# Sheet.net
KiCad netlist of a schematic drawn in Altium Designer
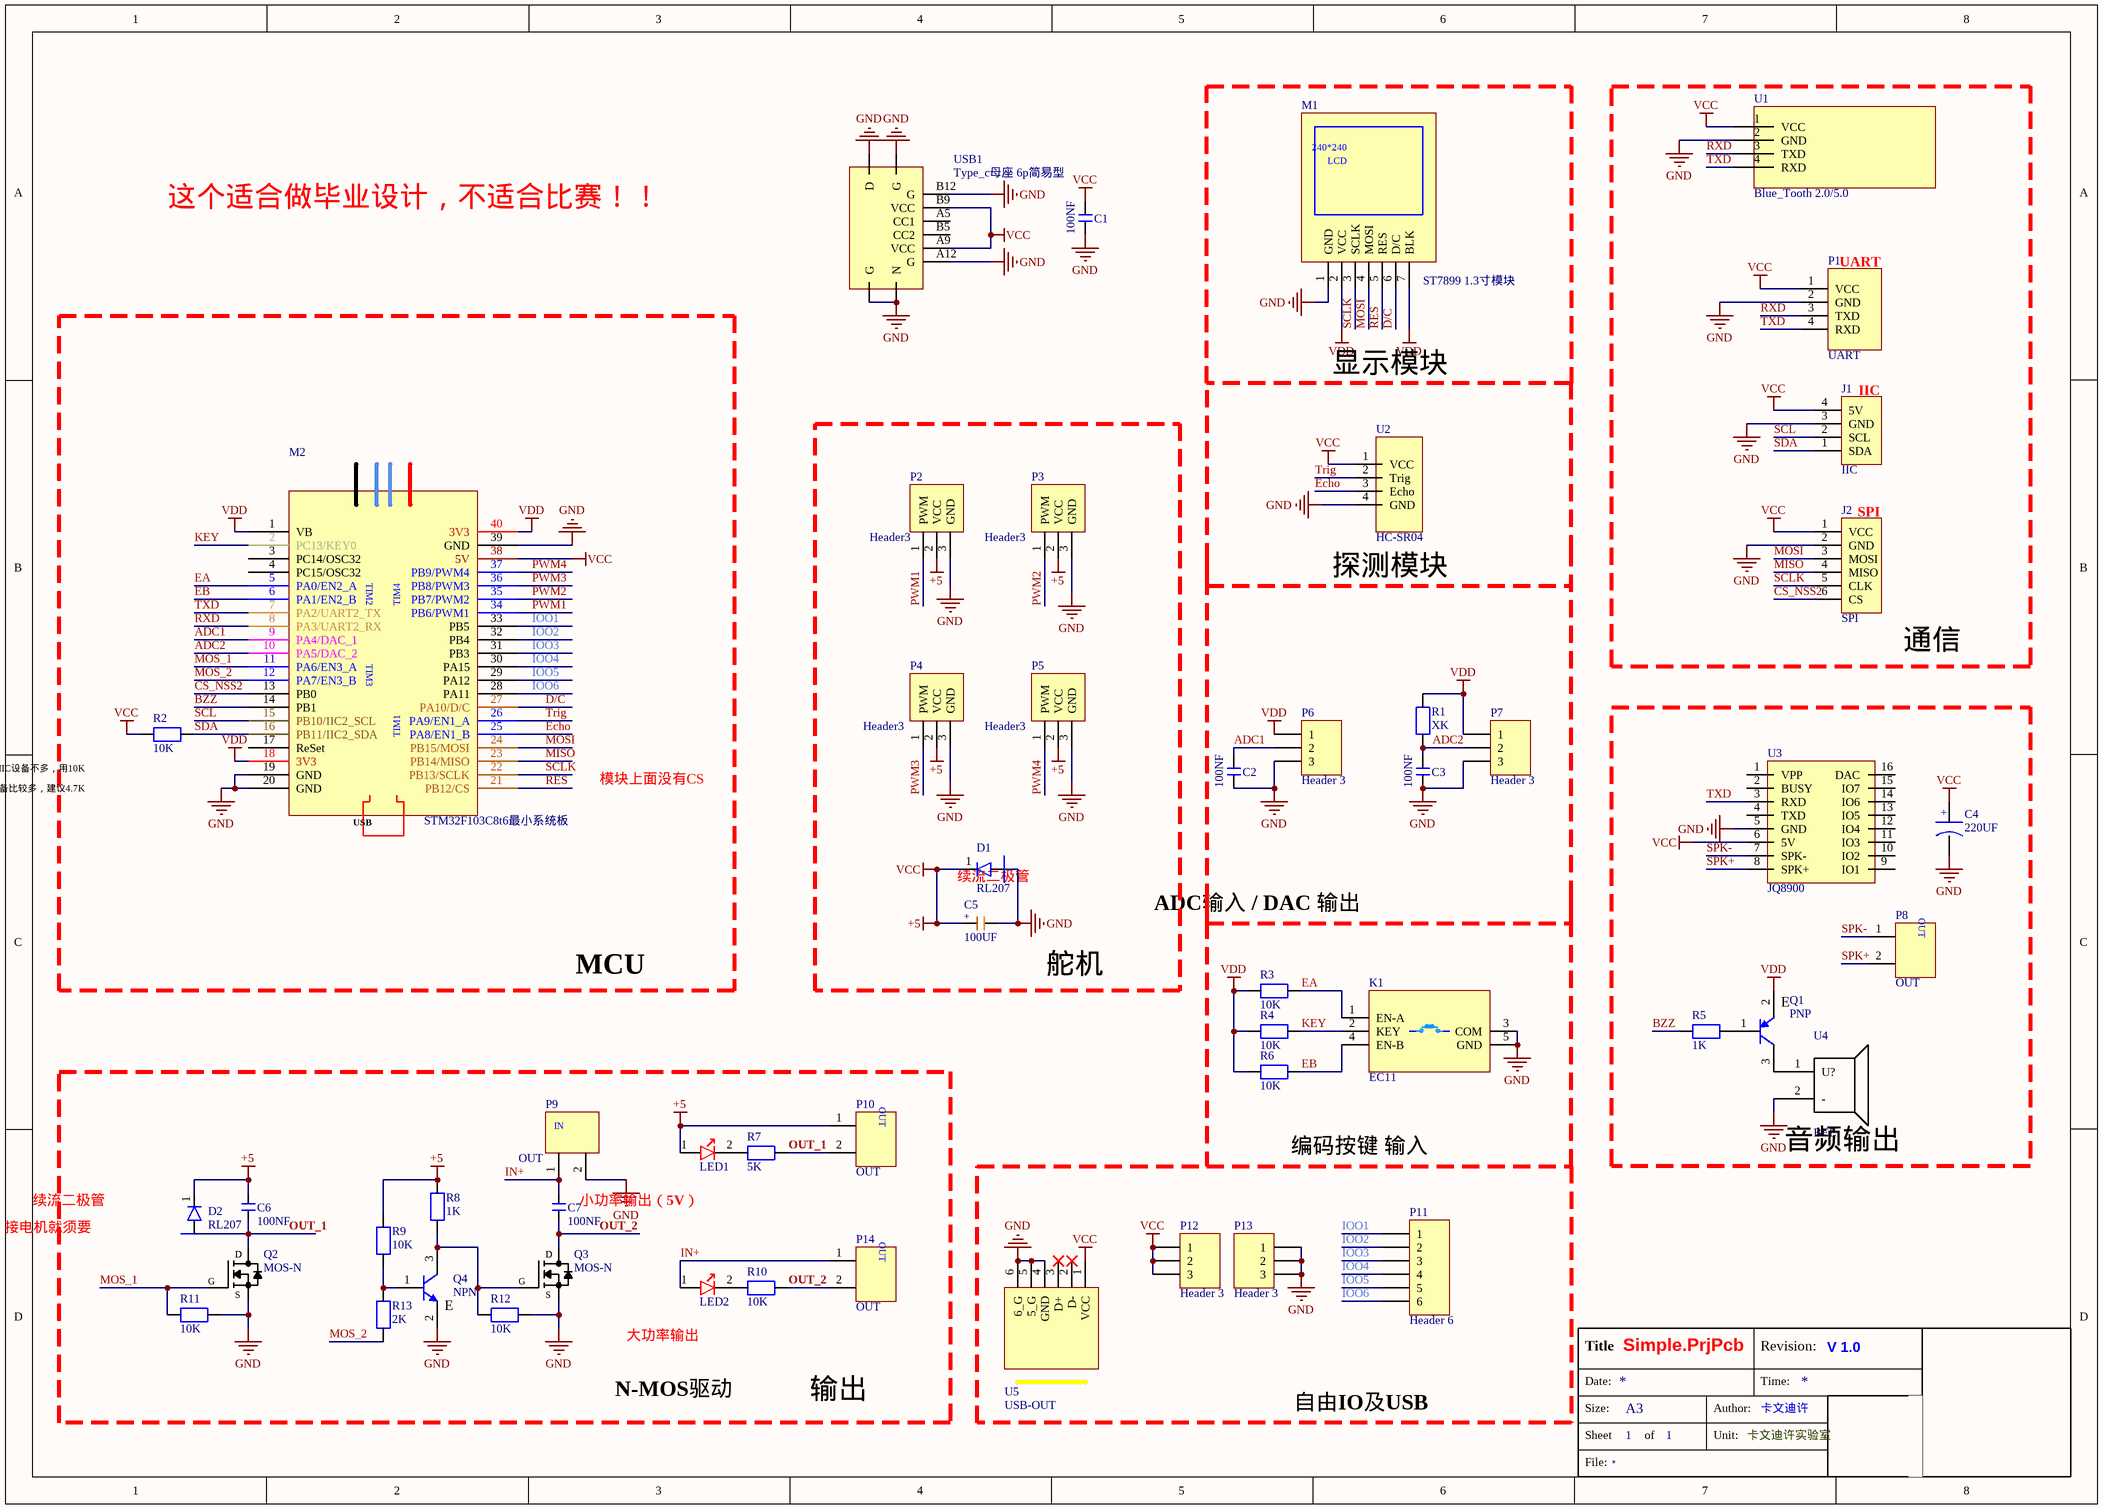
[diagram p0: Sheet.SchDoc]

(export (version "E")
  (design (tool "Eeschema 10.0.6"))
  (components
    (comp (ref "C1")
      (value "100NF")
      (footprint "CAP_0603")
      (description "CAP  12~50V")
      (libsource (lib "") (part "CAP_1"))
    )
    (comp (ref "C2")
      (value "100NF")
      (footprint "CAP_0603")
      (description "CAP  12~50V")
      (libsource (lib "") (part "CAP_1"))
    )
    (comp (ref "C3")
      (value "100NF")
      (footprint "CAP_0603")
      (description "CAP  12~50V")
      (libsource (lib "") (part "CAP_1"))
    )
    (comp (ref "C4")
      (value "220UF")
      (footprint "CAP_PR_2.5_6.3_RA")
      (description "CAP 12V ~ 50V   电解电容")
      (libsource (lib "User") (part "CAP_BIG"))
    )
    (comp (ref "C5")
      (value "100UF")
      (footprint "CAP_3528_B")
      (description "CAP  6~12V  钽电容")
      (libsource (lib "User") (part "CAP_TA"))
    )
    (comp (ref "C6")
      (value "100NF")
      (footprint "CAP_0603")
      (description "CAP  12~50V")
      (libsource (lib "User") (part "CAP"))
    )
    (comp (ref "C7")
      (value "100NF")
      (footprint "CAP_0603")
      (description "CAP  12~50V")
      (libsource (lib "User") (part "CAP"))
    )
    (comp (ref "D1")
      (value "RL207")
      (footprint "Diode_DO15")
      (description "Diode_肖特基/二极管 \r\n直插")
      (libsource (lib "User") (part "Diode-DO"))
    )
    (comp (ref "D2")
      (value "RL207")
      (footprint "Diode_DO15")
      (description "Diode_肖特基/二极管 \r\n直插")
      (libsource (lib "User") (part "Diode-DO"))
    )
    (comp (ref "J1")
      (value "IIC")
      (footprint "IIC-XH2.54-4PIN")
      (description "MLX90614 GY-906-BCC")
      (libsource (lib "User") (part "IIC"))
    )
    (comp (ref "J2")
      (value "SPI")
      (footprint "Header 2.54X6")
      (description "Heard")
      (libsource (lib "User") (part "SPI"))
    )
    (comp (ref "K1")
      (value "EC11")
      (footprint "EC-11")
      (description "KEY")
      (libsource (lib "User") (part "EN-CODE"))
    )
    (comp (ref "LED1")
      (value "LED_R/G/B/Y")
      (footprint "LED_5MM")
      (description "LED 5MM")
      (libsource (lib "User") (part "LED"))
    )
    (comp (ref "LED2")
      (value "LED_R/G/B/Y")
      (footprint "LED_5MM")
      (description "LED 5MM")
      (libsource (lib "User") (part "LED"))
    )
    (comp (ref "M1")
      (value "ST7899 1.3寸模块")
      (footprint "LCD_1.3_MODE")
      (description "SHOW")
      (libsource (lib "User") (part "LCD_TFT_1.3_MODE"))
    )
    (comp (ref "M2")
      (value "STM32F103C8t6最小系统板")
      (footprint "STM32F103C8_Simple")
      (description "Mode STM32F103C8t6最小系统板")
      (libsource (lib "User") (part "STM32F103C-Sys"))
    )
    (comp (ref "P1")
      (value "UART")
      (footprint "UART")
      (description "Header XH2.54 弯针座 4PIN")
      (libsource (lib "User") (part "UART"))
    )
    (comp (ref "P2")
      (value "Header3")
      (footprint "PWM_Steer-F")
      (description "Header")
      (libsource (lib "User") (part "PWM_D"))
    )
    (comp (ref "P3")
      (value "Header3")
      (footprint "PWM_Steer-B")
      (description "Header")
      (libsource (lib "User") (part "PWM_D"))
    )
    (comp (ref "P4")
      (value "Header3")
      (footprint "PWM_Steer-F")
      (description "Header")
      (libsource (lib "User") (part "PWM_D"))
    )
    (comp (ref "P5")
      (value "Header3")
      (footprint "PWM_Steer-B")
      (description "Header")
      (libsource (lib "User") (part "PWM_D"))
    )
    (comp (ref "P6")
      (value "Header 3")
      (footprint "Header 2.54X3")
      (description "Header, 3-Pin")
      (fields (field (name "PUBLISHER") "Altium Limited"))
      (libsource (lib "") (part "Header 3_1"))
    )
    (comp (ref "P7")
      (value "Header 3")
      (footprint "Header 2.54X3")
      (description "Header, 3-Pin")
      (fields (field (name "PUBLISHER") "Altium Limited"))
      (libsource (lib "") (part "Header 3_1"))
    )
    (comp (ref "P8")
      (value "OUT")
      (footprint "XH2.54-WI-2P")
      (description "Header")
      (libsource (lib "User") (part "OUT_2PIN"))
    )
    (comp (ref "P9")
      (value "OUT")
      (footprint "XT60-PW-M20")
      (description "Header")
      (libsource (lib "User") (part "IN _2PIN"))
    )
    (comp (ref "P10")
      (value "OUT")
      (footprint "Header 2.54X2")
      (description "Header")
      (libsource (lib "User") (part "OUT_2PIN"))
    )
    (comp (ref "P11")
      (value "Header 6")
      (footprint "Header 2.54X6")
      (description "Header, 6-Pin")
      (fields (field (name "PUBLISHER") "Altium Limited"))
      (libsource (lib "Miscellaneous Connectors") (part "Header 6"))
    )
    (comp (ref "P12")
      (value "Header 3")
      (footprint "Header 2.54X3")
      (description "Header, 3-Pin")
      (fields (field (name "PUBLISHER") "Altium Limited"))
      (libsource (lib "") (part "Header 3_1"))
    )
    (comp (ref "P13")
      (value "Header 3")
      (footprint "Header 2.54X3")
      (description "Header, 3-Pin")
      (fields (field (name "PUBLISHER") "Altium Limited"))
      (libsource (lib "Miscellaneous Connectors") (part "Header 3"))
    )
    (comp (ref "P14")
      (value "OUT")
      (footprint "PIN-2_5.08")
      (description "Header KF127a-5.08-2PIN")
      (libsource (lib "User") (part "OUT_2PIN"))
    )
    (comp (ref "Q1") (value "PNP") (footprint "SOT23_3") (libsource (lib "User") (part "PNP")))
    (comp (ref "Q2")
      (value "MOS-N")
      (footprint "SOT23_3")
      (description "MOSFET N-CH SI2308")
      (fields
        (field (name "MANUFACTURER") "ON Semiconductor")
        (field (name "MANUFACTURER PART NUMBER") "NTMFS5C628NLT1G")
      )
      (libsource (lib "User") (part "MOS-N"))
    )
    (comp (ref "Q3")
      (value "MOS-N")
      (footprint "TO252_2")
      (description "MOSFET N-CH NCE3050K")
      (fields
        (field (name "MANUFACTURER") "ON Semiconductor")
        (field (name "MANUFACTURER PART NUMBER") "NTMFS5C628NLT1G")
      )
      (libsource (lib "User") (part "MOS-N"))
    )
    (comp (ref "Q4") (value "NPN") (footprint "SOT23_3") (libsource (lib "User") (part "NPN")))
    (comp (ref "R1")
      (value "XK")
      (footprint "RES_0.4_1/4W")
      (description "RES 贴片")
      (libsource (lib "User") (part "RES_S"))
    )
    (comp (ref "R2")
      (value "10K")
      (footprint "RES_0.4_1/4W")
      (description "RES 贴片")
      (libsource (lib "User") (part "RES_S"))
    )
    (comp (ref "R3")
      (value "10K")
      (footprint "RES_0.4_1/4W")
      (description "RES 贴片")
      (libsource (lib "User") (part "RES_S"))
    )
    (comp (ref "R4")
      (value "10K")
      (footprint "RES_0.4_1/4W")
      (description "RES 贴片")
      (libsource (lib "User") (part "RES_S"))
    )
    (comp (ref "R5")
      (value "1K")
      (footprint "RES_0.4_1/4W")
      (description "RES 贴片")
      (libsource (lib "User") (part "RES_S"))
    )
    (comp (ref "R6")
      (value "10K")
      (footprint "RES_0.4_1/4W")
      (description "RES 贴片")
      (libsource (lib "User") (part "RES_S"))
    )
    (comp (ref "R7")
      (value "5K")
      (footprint "RES_0.4_1/4W")
      (description "RES 贴片")
      (libsource (lib "User") (part "RES_S"))
    )
    (comp (ref "R8")
      (value "1K")
      (footprint "RES_0.4_1/4W")
      (description "RES 贴片")
      (libsource (lib "User") (part "RES_S"))
    )
    (comp (ref "R9")
      (value "10K")
      (footprint "RES_0.4_1/4W")
      (description "RES 贴片")
      (libsource (lib "User") (part "RES_S"))
    )
    (comp (ref "R10")
      (value "10K")
      (footprint "RES_0.4_1/4W")
      (description "RES 贴片")
      (libsource (lib "User") (part "RES_S"))
    )
    (comp (ref "R11")
      (value "10K")
      (footprint "RES_0.4_1/4W")
      (description "RES 贴片")
      (libsource (lib "User") (part "RES_S"))
    )
    (comp (ref "R12")
      (value "10K")
      (footprint "RES_0.4_1/4W")
      (description "RES 贴片")
      (libsource (lib "User") (part "RES_S"))
    )
    (comp (ref "R13")
      (value "2K")
      (footprint "RES_0.4_1/4W")
      (description "RES 贴片")
      (libsource (lib "User") (part "RES_S"))
    )
    (comp (ref "U1")
      (value "Blue_Tooth 2.0/5.0")
      (footprint "uart-Haerd")
      (description "MODE HC-06(记得买底座 排母-4PIN)")
      (libsource (lib "User") (part "HC-02/06"))
    )
    (comp (ref "U2")
      (value "HC-SR04")
      (footprint "Ultrasonic")
      (description "Mode")
      (libsource (lib "User") (part "Ultrasonic"))
    )
    (comp (ref "U3")
      (value "JQ8900")
      (footprint "SpkMo")
      (description "MODE")
      (libsource (lib "User") (part "SPKMO_8900"))
    )
    (comp (ref "U4") (value "BEE") (footprint "BEE-FMQ5mm") (libsource (lib "User") (part "BZZ")))
    (comp (ref "U5")
      (value "USB-OUT")
      (footprint "USB_Bout")
      (description "USB-A母 90 度 带后盖")
      (libsource (lib "User") (part "USB-OUT"))
    )
    (comp (ref "USB1")
      (value "Type_c母座 6p简易型")
      (footprint "USB-Type-c_6P")
      (description "USB")
      (libsource (lib "User") (part "USB-Type_c-6PIn"))
    )
  )
  (nets
    (net (code "1") (name "+5") (class "Default")
      (node (ref "C1") (pin "2") (pinfunction "0_2") (pintype "passive"))
      (node (ref "C4") (pin "1") (pinfunction "0_1") (pintype "passive"))
      (node (ref "C5") (pin "1") (pinfunction "0_1") (pintype "passive"))
      (node (ref "C6") (pin "2") (pinfunction "0_2") (pintype "passive"))
      (node (ref "D1") (pin "1") (pinfunction "N_1") (pintype "passive"))
      (node (ref "D2") (pin "1") (pinfunction "N_1") (pintype "passive"))
      (node (ref "J1") (pin "4") (pinfunction "5V_4") (pintype "passive"))
      (node (ref "J2") (pin "1") (pinfunction "VCC_1") (pintype "passive"))
      (node (ref "LED1") (pin "1") (pinfunction "+_1") (pintype "passive"))
      (node (ref "M2") (pin "38") (pinfunction "5V_38") (pintype "passive"))
      (node (ref "P1") (pin "1") (pinfunction "VCC_1") (pintype "passive"))
      (node (ref "P10") (pin "1") (pintype "passive"))
      (node (ref "P12") (pin "1") (pinfunction "1_1") (pintype "passive"))
      (node (ref "P12") (pin "2") (pinfunction "2_2") (pintype "passive"))
      (node (ref "P12") (pin "3") (pinfunction "3_3") (pintype "passive"))
      (node (ref "P2") (pin "2") (pinfunction "VCC_2") (pintype "passive"))
      (node (ref "P3") (pin "2") (pinfunction "VCC_2") (pintype "passive"))
      (node (ref "P4") (pin "2") (pinfunction "VCC_2") (pintype "passive"))
      (node (ref "P5") (pin "2") (pinfunction "VCC_2") (pintype "passive"))
      (node (ref "R2") (pin "1") (pinfunction "1_1") (pintype "passive"))
      (node (ref "R8") (pin "1") (pinfunction "1_1") (pintype "passive"))
      (node (ref "R9") (pin "2") (pinfunction "2_2") (pintype "passive"))
      (node (ref "U1") (pin "1") (pinfunction "VCC_1") (pintype "passive"))
      (node (ref "U2") (pin "1") (pinfunction "VCC_1") (pintype "passive"))
      (node (ref "U3") (pin "6") (pinfunction "5V_6") (pintype "passive"))
      (node (ref "U5") (pin "1") (pinfunction "VCC_1") (pintype "passive"))
      (node (ref "USB1") (pin "A9") (pinfunction "VCC_A9") (pintype "passive"))
      (node (ref "USB1") (pin "B9") (pinfunction "VCC_B9") (pintype "passive"))
    )
    (net (code "2") (name "/ADC1") (class "Default")
      (node (ref "C2") (pin "2") (pinfunction "0_2") (pintype "passive"))
      (node (ref "M2") (pin "9") (pinfunction "PA4/DAC_1_9") (pintype "passive"))
      (node (ref "P6") (pin "2") (pinfunction "2_2") (pintype "passive"))
    )
    (net (code "3") (name "/ADC2") (class "Default")
      (node (ref "C3") (pin "2") (pinfunction "0_2") (pintype "passive"))
      (node (ref "M2") (pin "10") (pinfunction "PA5/DAC_2_10") (pintype "passive"))
      (node (ref "P7") (pin "2") (pinfunction "2_2") (pintype "passive"))
      (node (ref "R1") (pin "1") (pinfunction "1_1") (pintype "passive"))
    )
    (net (code "4") (name "/BZZ") (class "Default")
      (node (ref "M2") (pin "14") (pinfunction "PB1_14") (pintype "passive"))
      (node (ref "R5") (pin "1") (pinfunction "1_1") (pintype "passive"))
    )
    (net (code "5") (name "/CS_NSS2") (class "Default")
      (node (ref "J2") (pin "6") (pinfunction "CS_6") (pintype "passive"))
      (node (ref "M2") (pin "13") (pinfunction "PB0_13") (pintype "passive"))
    )
    (net (code "6") (name "/D{slash}C") (class "Default")
      (node (ref "M1") (pin "6") (pinfunction "D/C_6") (pintype "passive"))
      (node (ref "M2") (pin "27") (pinfunction "PA10/D/C_27") (pintype "passive"))
    )
    (net (code "7") (name "/EA") (class "Default")
      (node (ref "K1") (pin "1") (pinfunction "EN-A_1") (pintype "passive"))
      (node (ref "M2") (pin "5") (pinfunction "PA0/EN2_A_5") (pintype "passive"))
      (node (ref "R3") (pin "2") (pinfunction "2_2") (pintype "passive"))
    )
    (net (code "8") (name "/EB") (class "Default")
      (node (ref "K1") (pin "4") (pinfunction "EN-B_4") (pintype "passive"))
      (node (ref "M2") (pin "6") (pinfunction "PA1/EN2_B_6") (pintype "passive"))
      (node (ref "R6") (pin "2") (pinfunction "2_2") (pintype "passive"))
    )
    (net (code "9") (name "/Echo") (class "Default")
      (node (ref "M2") (pin "25") (pinfunction "PA8/EN1_B_25") (pintype "passive"))
      (node (ref "U2") (pin "3") (pinfunction "Echo_3") (pintype "passive"))
    )
    (net (code "10") (name "/IN+") (class "Default")
      (node (ref "C7") (pin "2") (pinfunction "0_2") (pintype "passive"))
      (node (ref "LED2") (pin "1") (pinfunction "+_1") (pintype "passive"))
      (node (ref "P14") (pin "1") (pintype "passive"))
      (node (ref "P9") (pin "1") (pintype "passive"))
    )
    (net (code "11") (name "/IOO1") (class "Default")
      (node (ref "M2") (pin "33") (pinfunction "PB5_33") (pintype "passive"))
      (node (ref "P11") (pin "1") (pinfunction "1_1") (pintype "passive"))
    )
    (net (code "12") (name "/IOO2") (class "Default")
      (node (ref "M2") (pin "32") (pinfunction "PB4_32") (pintype "passive"))
      (node (ref "P11") (pin "2") (pinfunction "2_2") (pintype "passive"))
    )
    (net (code "13") (name "/IOO3") (class "Default")
      (node (ref "M2") (pin "31") (pinfunction "PB3_31") (pintype "passive"))
      (node (ref "P11") (pin "3") (pinfunction "3_3") (pintype "passive"))
    )
    (net (code "14") (name "/IOO4") (class "Default")
      (node (ref "M2") (pin "30") (pinfunction "PA15_30") (pintype "passive"))
      (node (ref "P11") (pin "4") (pinfunction "4_4") (pintype "passive"))
    )
    (net (code "15") (name "/IOO5") (class "Default")
      (node (ref "M2") (pin "29") (pinfunction "PA12_29") (pintype "passive"))
      (node (ref "P11") (pin "5") (pinfunction "5_5") (pintype "passive"))
    )
    (net (code "16") (name "/IOO6") (class "Default")
      (node (ref "M2") (pin "28") (pinfunction "PA11_28") (pintype "passive"))
      (node (ref "P11") (pin "6") (pinfunction "6_6") (pintype "passive"))
    )
    (net (code "17") (name "/KEY") (class "Default")
      (node (ref "K1") (pin "2") (pinfunction "KEY_2") (pintype "passive"))
      (node (ref "M2") (pin "2") (pinfunction "PC13/KEY0_2") (pintype "passive"))
      (node (ref "R4") (pin "2") (pinfunction "2_2") (pintype "passive"))
    )
    (net (code "18") (name "/MISO") (class "Default")
      (node (ref "J2") (pin "4") (pinfunction "MISO_4") (pintype "passive"))
      (node (ref "M2") (pin "23") (pinfunction "PB14/MISO_23") (pintype "passive"))
    )
    (net (code "19") (name "/MOSI") (class "Default")
      (node (ref "J2") (pin "3") (pinfunction "MOSI_3") (pintype "passive"))
      (node (ref "M1") (pin "4") (pinfunction "MOSI_4") (pintype "passive"))
      (node (ref "M2") (pin "24") (pinfunction "PB15/MOSI_24") (pintype "passive"))
    )
    (net (code "20") (name "/MOS_1") (class "Default")
      (node (ref "M2") (pin "11") (pinfunction "PA6/EN3_A_11") (pintype "passive"))
      (node (ref "Q2") (pin "1") (pinfunction "G_1") (pintype "passive"))
      (node (ref "R11") (pin "1") (pinfunction "1_1") (pintype "passive"))
    )
    (net (code "21") (name "/MOS_2") (class "Default")
      (node (ref "M2") (pin "12") (pinfunction "PA7/EN3_B_12") (pintype "passive"))
      (node (ref "R13") (pin "1") (pinfunction "1_1") (pintype "passive"))
    )
    (net (code "22") (name "/OUT_1") (class "Default")
      (node (ref "C6") (pin "1") (pinfunction "0_1") (pintype "passive"))
      (node (ref "D2") (pin "2") (pinfunction "P_2") (pintype "passive"))
      (node (ref "P10") (pin "2") (pintype "passive"))
      (node (ref "Q2") (pin "3") (pinfunction "D_3") (pintype "passive"))
      (node (ref "R7") (pin "2") (pinfunction "2_2") (pintype "passive"))
    )
    (net (code "23") (name "/OUT_2") (class "Default")
      (node (ref "C7") (pin "1") (pinfunction "0_1") (pintype "passive"))
      (node (ref "P14") (pin "2") (pintype "passive"))
      (node (ref "Q3") (pin "3") (pinfunction "D_3") (pintype "passive"))
      (node (ref "R10") (pin "2") (pinfunction "2_2") (pintype "passive"))
    )
    (net (code "24") (name "/PWM1") (class "Default")
      (node (ref "M2") (pin "34") (pinfunction "PB6/PWM1_34") (pintype "passive"))
      (node (ref "P2") (pin "1") (pinfunction "PWM_1") (pintype "passive"))
    )
    (net (code "25") (name "/PWM2") (class "Default")
      (node (ref "M2") (pin "35") (pinfunction "PB7/PWM2_35") (pintype "passive"))
      (node (ref "P3") (pin "1") (pinfunction "PWM_1") (pintype "passive"))
    )
    (net (code "26") (name "/PWM3") (class "Default")
      (node (ref "M2") (pin "36") (pinfunction "PB8/PWM3_36") (pintype "passive"))
      (node (ref "P4") (pin "1") (pinfunction "PWM_1") (pintype "passive"))
    )
    (net (code "27") (name "/PWM4") (class "Default")
      (node (ref "M2") (pin "37") (pinfunction "PB9/PWM4_37") (pintype "passive"))
      (node (ref "P5") (pin "1") (pinfunction "PWM_1") (pintype "passive"))
    )
    (net (code "28") (name "/RES") (class "Default")
      (node (ref "M1") (pin "5") (pinfunction "RES_5") (pintype "passive"))
      (node (ref "M2") (pin "21") (pinfunction "PB12/CS_21") (pintype "passive"))
    )
    (net (code "29") (name "/RXD") (class "Default")
      (node (ref "M2") (pin "8") (pinfunction "PA3/UART2_RX_8") (pintype "passive"))
      (node (ref "P1") (pin "3") (pinfunction "TXD_3") (pintype "passive"))
      (node (ref "U1") (pin "3") (pinfunction "TXD_3") (pintype "passive"))
    )
    (net (code "30") (name "/SCL") (class "Default")
      (node (ref "J1") (pin "2") (pinfunction "SCL_2") (pintype "passive"))
      (node (ref "M2") (pin "15") (pinfunction "PB10/IIC2_SCL_15") (pintype "passive"))
    )
    (net (code "31") (name "/SCLK") (class "Default")
      (node (ref "J2") (pin "5") (pinfunction "CLK_5") (pintype "passive"))
      (node (ref "M1") (pin "3") (pinfunction "SCLK_3") (pintype "passive"))
      (node (ref "M2") (pin "22") (pinfunction "PB13/SCLK_22") (pintype "passive"))
    )
    (net (code "32") (name "/SDA") (class "Default")
      (node (ref "J1") (pin "1") (pinfunction "SDA_1") (pintype "passive"))
      (node (ref "M2") (pin "16") (pinfunction "PB11/IIC2_SDA_16") (pintype "passive"))
      (node (ref "R2") (pin "2") (pinfunction "2_2") (pintype "passive"))
    )
    (net (code "33") (name "/SPK+") (class "Default")
      (node (ref "P8") (pin "2") (pintype "passive"))
      (node (ref "U3") (pin "8") (pinfunction "SPK+_8") (pintype "passive"))
    )
    (net (code "34") (name "/SPK-") (class "Default")
      (node (ref "P8") (pin "1") (pintype "passive"))
      (node (ref "U3") (pin "7") (pinfunction "SPK-_7") (pintype "passive"))
    )
    (net (code "35") (name "/TXD") (class "Default")
      (node (ref "M2") (pin "7") (pinfunction "PA2/UART2_TX_7") (pintype "passive"))
      (node (ref "P1") (pin "4") (pinfunction "RXD_4") (pintype "passive"))
      (node (ref "U1") (pin "4") (pinfunction "RXD_4") (pintype "passive"))
      (node (ref "U3") (pin "3") (pinfunction "RXD_3") (pintype "passive"))
    )
    (net (code "36") (name "/Trig") (class "Default")
      (node (ref "M2") (pin "26") (pinfunction "PA9/EN1_A_26") (pintype "passive"))
      (node (ref "U2") (pin "2") (pinfunction "Trig_2") (pintype "passive"))
    )
    (net (code "37") (name "GND") (class "Default")
      (node (ref "C1") (pin "1") (pinfunction "0_1") (pintype "passive"))
      (node (ref "C2") (pin "1") (pinfunction "0_1") (pintype "passive"))
      (node (ref "C3") (pin "1") (pinfunction "0_1") (pintype "passive"))
      (node (ref "C4") (pin "2") (pinfunction "0_2") (pintype "passive"))
      (node (ref "C5") (pin "2") (pinfunction "0_2") (pintype "passive"))
      (node (ref "D1") (pin "2") (pinfunction "P_2") (pintype "passive"))
      (node (ref "J1") (pin "3") (pinfunction "GND_3") (pintype "passive"))
      (node (ref "J2") (pin "2") (pinfunction "GND_2") (pintype "passive"))
      (node (ref "K1") (pin "3") (pinfunction "COM_3") (pintype "passive"))
      (node (ref "K1") (pin "5") (pinfunction "GND_5") (pintype "passive"))
      (node (ref "M1") (pin "1") (pinfunction "GND_1") (pintype "passive"))
      (node (ref "M2") (pin "19") (pinfunction "GND_19") (pintype "passive"))
      (node (ref "M2") (pin "20") (pinfunction "GND_20") (pintype "passive"))
      (node (ref "M2") (pin "39") (pinfunction "GND_39") (pintype "passive"))
      (node (ref "P1") (pin "2") (pinfunction "GND_2") (pintype "passive"))
      (node (ref "P13") (pin "1") (pinfunction "1_1") (pintype "passive"))
      (node (ref "P13") (pin "2") (pinfunction "2_2") (pintype "passive"))
      (node (ref "P13") (pin "3") (pinfunction "3_3") (pintype "passive"))
      (node (ref "P2") (pin "3") (pinfunction "GND_3") (pintype "passive"))
      (node (ref "P3") (pin "3") (pinfunction "GND_3") (pintype "passive"))
      (node (ref "P4") (pin "3") (pinfunction "GND_3") (pintype "passive"))
      (node (ref "P5") (pin "3") (pinfunction "GND_3") (pintype "passive"))
      (node (ref "P6") (pin "3") (pinfunction "3_3") (pintype "passive"))
      (node (ref "P7") (pin "3") (pinfunction "3_3") (pintype "passive"))
      (node (ref "P9") (pin "2") (pintype "passive"))
      (node (ref "Q2") (pin "2") (pinfunction "S_2") (pintype "passive"))
      (node (ref "Q3") (pin "2") (pinfunction "S_2") (pintype "passive"))
      (node (ref "Q4") (pin "2") (pinfunction "E_2") (pintype "passive"))
      (node (ref "R11") (pin "2") (pinfunction "2_2") (pintype "passive"))
      (node (ref "R12") (pin "2") (pinfunction "2_2") (pintype "passive"))
      (node (ref "U1") (pin "2") (pinfunction "GND_2") (pintype "passive"))
      (node (ref "U2") (pin "4") (pinfunction "GND_4") (pintype "passive"))
      (node (ref "U3") (pin "5") (pinfunction "GND_5") (pintype "passive"))
      (node (ref "U4") (pin "2") (pinfunction "-_2") (pintype "passive"))
      (node (ref "U5") (pin "4") (pinfunction "GND_4") (pintype "passive"))
      (node (ref "U5") (pin "5") (pinfunction "5_G_5") (pintype "passive"))
      (node (ref "U5") (pin "6") (pinfunction "6_G_6") (pintype "passive"))
      (node (ref "USB1") (pin "A") (pinfunction "G_A") (pintype "passive"))
      (node (ref "USB1") (pin "A12") (pinfunction "G_A12") (pintype "passive"))
      (node (ref "USB1") (pin "B") (pinfunction "N_B") (pintype "passive"))
      (node (ref "USB1") (pin "B12") (pinfunction "G_B12") (pintype "passive"))
      (node (ref "USB1") (pin "C") (pinfunction "D_C") (pintype "passive"))
      (node (ref "USB1") (pin "D") (pinfunction "G_D") (pintype "passive"))
    )
    (net (code "38") (name "Net-(LED1--)") (class "Default")
      (node (ref "LED1") (pin "2") (pinfunction "-_2") (pintype "passive"))
      (node (ref "R7") (pin "1") (pinfunction "1_1") (pintype "passive"))
    )
    (net (code "39") (name "Net-(LED2--)") (class "Default")
      (node (ref "LED2") (pin "2") (pinfunction "-_2") (pintype "passive"))
      (node (ref "R10") (pin "1") (pinfunction "1_1") (pintype "passive"))
    )
    (net (code "40") (name "Net-(Q1-B)") (class "Default")
      (node (ref "Q1") (pin "1") (pinfunction "B_1") (pintype "passive"))
      (node (ref "R5") (pin "2") (pinfunction "2_2") (pintype "passive"))
    )
    (net (code "41") (name "Net-(Q1-C)") (class "Default")
      (node (ref "Q1") (pin "3") (pinfunction "C_3") (pintype "passive"))
      (node (ref "U4") (pin "1") (pinfunction "U?_1") (pintype "passive"))
    )
    (net (code "42") (name "Net-(Q3-G)") (class "Default")
      (node (ref "Q3") (pin "1") (pinfunction "G_1") (pintype "passive"))
      (node (ref "Q4") (pin "3") (pinfunction "C_3") (pintype "passive"))
      (node (ref "R12") (pin "1") (pinfunction "1_1") (pintype "passive"))
      (node (ref "R8") (pin "2") (pinfunction "2_2") (pintype "passive"))
    )
    (net (code "43") (name "Net-(Q4-B)") (class "Default")
      (node (ref "Q4") (pin "1") (pinfunction "B_1") (pintype "passive"))
      (node (ref "R13") (pin "2") (pinfunction "2_2") (pintype "passive"))
      (node (ref "R9") (pin "1") (pinfunction "1_1") (pintype "passive"))
    )
    (net (code "44") (name "VDD") (class "Default")
      (node (ref "M1") (pin "2") (pinfunction "VCC_2") (pintype "passive"))
      (node (ref "M1") (pin "7") (pinfunction "BLK_7") (pintype "passive"))
      (node (ref "M2") (pin "1") (pinfunction "VB_1") (pintype "passive"))
      (node (ref "M2") (pin "18") (pinfunction "3V3_18") (pintype "passive"))
      (node (ref "M2") (pin "40") (pinfunction "3V3_40") (pintype "passive"))
      (node (ref "P6") (pin "1") (pinfunction "1_1") (pintype "passive"))
      (node (ref "P7") (pin "1") (pinfunction "1_1") (pintype "passive"))
      (node (ref "Q1") (pin "2") (pinfunction "E_2") (pintype "passive"))
      (node (ref "R1") (pin "2") (pinfunction "2_2") (pintype "passive"))
      (node (ref "R3") (pin "1") (pinfunction "1_1") (pintype "passive"))
      (node (ref "R4") (pin "1") (pinfunction "1_1") (pintype "passive"))
      (node (ref "R6") (pin "1") (pinfunction "1_1") (pintype "passive"))
    )
    (net (code "45") (name "unconnected-(M2-PC14{slash}OSC32-Pad3)") (class "Default")
      (node (ref "M2") (pin "3") (pinfunction "PC14/OSC32_3") (pintype "passive"))
    )
    (net (code "46") (name "unconnected-(M2-PC15{slash}OSC32-Pad4)") (class "Default")
      (node (ref "M2") (pin "4") (pinfunction "PC15/OSC32_4") (pintype "passive"))
    )
    (net (code "47") (name "unconnected-(M2-ReSet-Pad17)") (class "Default")
      (node (ref "M2") (pin "17") (pinfunction "ReSet_17") (pintype "passive"))
    )
    (net (code "48") (name "unconnected-(U3-BUSY-Pad2)") (class "Default")
      (node (ref "U3") (pin "2") (pinfunction "BUSY_2") (pintype "passive"))
    )
    (net (code "49") (name "unconnected-(U3-DAC-Pad16)") (class "Default")
      (node (ref "U3") (pin "16") (pinfunction "DAC_16") (pintype "passive"))
    )
    (net (code "50") (name "unconnected-(U3-IO1-Pad9)") (class "Default")
      (node (ref "U3") (pin "9") (pinfunction "IO1_9") (pintype "passive"))
    )
    (net (code "51") (name "unconnected-(U3-IO2-Pad10)") (class "Default")
      (node (ref "U3") (pin "10") (pinfunction "IO2_10") (pintype "passive"))
    )
    (net (code "52") (name "unconnected-(U3-IO3-Pad11)") (class "Default")
      (node (ref "U3") (pin "11") (pinfunction "IO3_11") (pintype "passive"))
    )
    (net (code "53") (name "unconnected-(U3-IO4-Pad12)") (class "Default")
      (node (ref "U3") (pin "12") (pinfunction "IO4_12") (pintype "passive"))
    )
    (net (code "54") (name "unconnected-(U3-IO5-Pad13)") (class "Default")
      (node (ref "U3") (pin "13") (pinfunction "IO5_13") (pintype "passive"))
    )
    (net (code "55") (name "unconnected-(U3-IO6-Pad14)") (class "Default")
      (node (ref "U3") (pin "14") (pinfunction "IO6_14") (pintype "passive"))
    )
    (net (code "56") (name "unconnected-(U3-IO7-Pad15)") (class "Default")
      (node (ref "U3") (pin "15") (pinfunction "IO7_15") (pintype "passive"))
    )
    (net (code "57") (name "unconnected-(U3-TXD-Pad4)") (class "Default")
      (node (ref "U3") (pin "4") (pinfunction "TXD_4") (pintype "passive"))
    )
    (net (code "58") (name "unconnected-(U3-VPP-Pad1)") (class "Default")
      (node (ref "U3") (pin "1") (pinfunction "VPP_1") (pintype "passive"))
    )
    (net (code "59") (name "unconnected-(U5-D+-Pad3)") (class "Default")
      (node (ref "U5") (pin "3") (pinfunction "D+_3") (pintype "passive+no_connect"))
    )
    (net (code "60") (name "unconnected-(U5-D--Pad2)") (class "Default")
      (node (ref "U5") (pin "2") (pinfunction "D-_2") (pintype "passive+no_connect"))
    )
    (net (code "61") (name "unconnected-(USB1-CC1-PadA5)") (class "Default")
      (node (ref "USB1") (pin "A5") (pinfunction "CC1_A5") (pintype "passive"))
    )
    (net (code "62") (name "unconnected-(USB1-CC2-PadB5)") (class "Default")
      (node (ref "USB1") (pin "B5") (pinfunction "CC2_B5") (pintype "passive"))
    )
  )
)
